# OpenSprinkler_v142.net
KiCad netlist of a schematic drawn in EAGLE
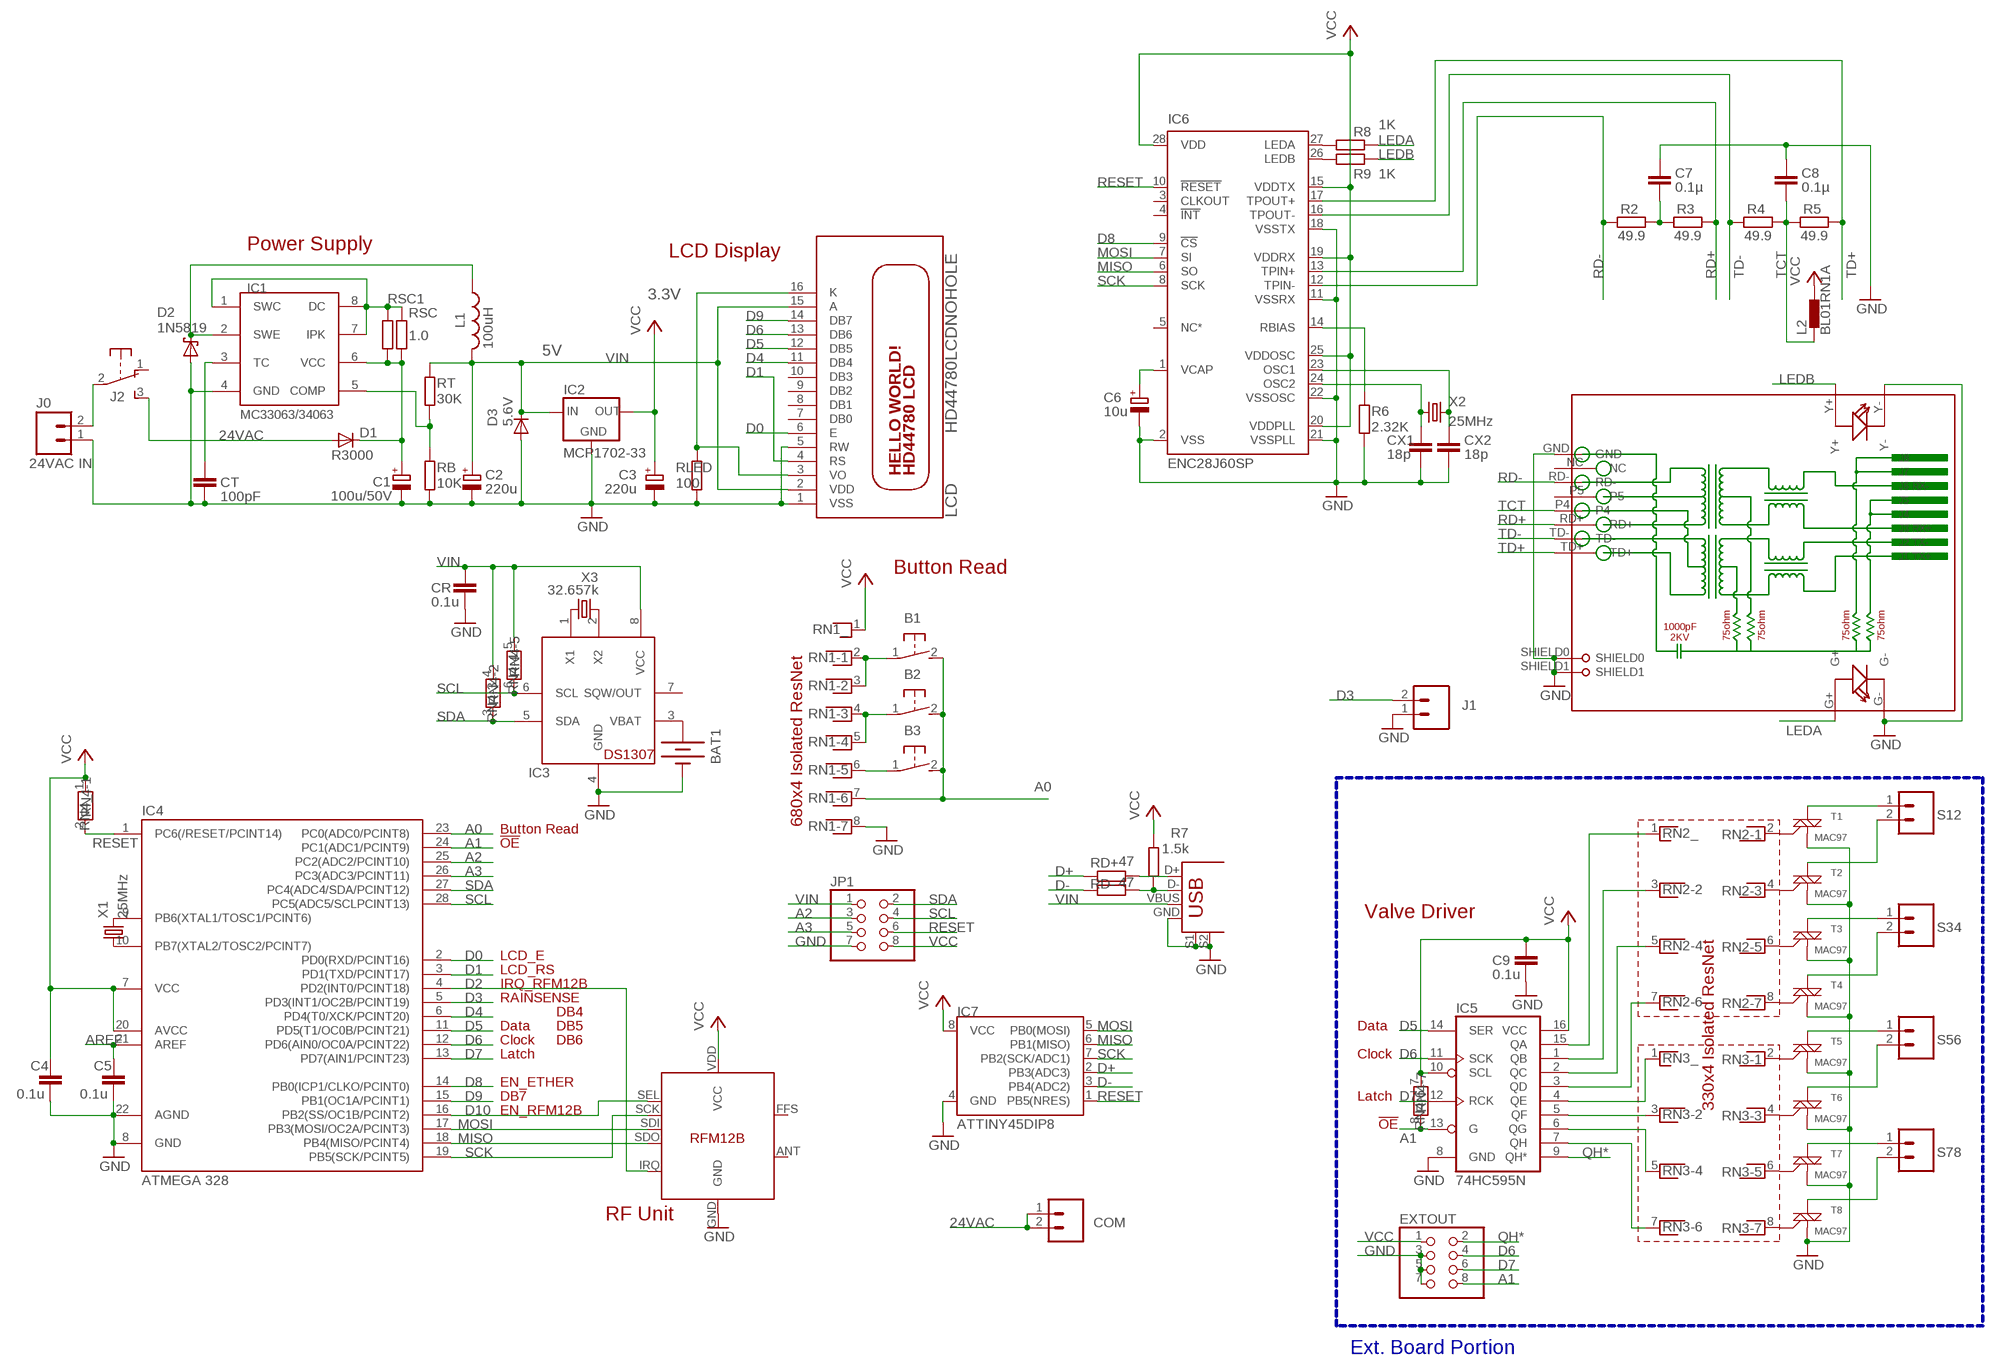
[diagram p0: schematic, sheet 1]

(export (version "E")
  (design (tool "Eeschema 10.0.6"))
  (components
    (comp (ref "B1")
      (value "31-XX")
      (footprint "eagle-import:B3F-31XX")
      (libsource (lib "eagle-import") (part "31-XX"))
    )
    (comp (ref "B2")
      (value "31-XX")
      (footprint "eagle-import:B3F-31XX")
      (libsource (lib "eagle-import") (part "31-XX"))
    )
    (comp (ref "B3")
      (value "31-XX")
      (footprint "eagle-import:B3F-31XX")
      (libsource (lib "eagle-import") (part "31-XX"))
    )
    (comp (ref "BAT1")
      (value "BATTERY12PTH")
      (footprint "eagle-import:BATTCON_12MM_PTH")
      (libsource (lib "eagle-import") (part "BATTERY12PTH"))
    )
    (comp (ref "C1")
      (value "100u/50V")
      (footprint "eagle-import:E3,5-8")
      (libsource (lib "eagle-import") (part "CPOL-EUE3.5-8"))
    )
    (comp (ref "C2")
      (value "220u")
      (footprint "eagle-import:E2-5")
      (libsource (lib "eagle-import") (part "CPOL-EUE2-5"))
    )
    (comp (ref "C3")
      (value "220u")
      (footprint "eagle-import:E2-5")
      (libsource (lib "eagle-import") (part "CPOL-EUE2-5"))
    )
    (comp (ref "C4")
      (value "0.1u")
      (footprint "eagle-import:C025-024X044")
      (libsource (lib "eagle-import") (part "C-EU025-024X044"))
    )
    (comp (ref "C5")
      (value "0.1u")
      (footprint "eagle-import:C025-024X044")
      (libsource (lib "eagle-import") (part "C-EU025-024X044"))
    )
    (comp (ref "C6")
      (value "10u")
      (footprint "eagle-import:E1,8-4")
      (libsource (lib "eagle-import") (part "CPOL-EUE1.8-4"))
    )
    (comp (ref "C7")
      (value "0.1µ")
      (footprint "eagle-import:C025-024X044")
      (libsource (lib "eagle-import") (part "resistor_C-EU025-024X044"))
    )
    (comp (ref "C8")
      (value "0.1µ")
      (footprint "eagle-import:C025-024X044")
      (libsource (lib "eagle-import") (part "resistor_C-EU025-024X044"))
    )
    (comp (ref "C9")
      (value "0.1u")
      (footprint "eagle-import:C025-024X044")
      (libsource (lib "eagle-import") (part "C-EU025-024X044"))
    )
    (comp (ref "COM")
      (value "M025MM")
      (footprint "eagle-import:SCREWTERMINAL-5MM-2")
      (libsource (lib "eagle-import") (part "M025MM"))
    )
    (comp (ref "CR")
      (value "0.1u")
      (footprint "eagle-import:C025-024X044")
      (libsource (lib "eagle-import") (part "C-EU025-024X044"))
    )
    (comp (ref "CT")
      (value "100pF")
      (footprint "eagle-import:C025-024X044")
      (libsource (lib "eagle-import") (part "C-EU025-024X044"))
    )
    (comp (ref "CX1")
      (value "18p")
      (footprint "eagle-import:C025-024X044")
      (libsource (lib "eagle-import") (part "resistor_C-EU025-024X044"))
    )
    (comp (ref "CX2")
      (value "18p")
      (footprint "eagle-import:C025-024X044")
      (libsource (lib "eagle-import") (part "resistor_C-EU025-024X044"))
    )
    (comp (ref "D1")
      (value "R3000")
      (footprint "eagle-import:DO41-7.6")
      (libsource (lib "eagle-import") (part "DIODE-DO41-7.6"))
    )
    (comp (ref "D2")
      (value "1N5819")
      (footprint "eagle-import:DO41-7.6")
      (libsource (lib "eagle-import") (part "1N5817-B"))
    )
    (comp (ref "D3")
      (value "5.6V")
      (footprint "eagle-import:DO35-7")
      (libsource (lib "eagle-import") (part "1N4148DO35-7"))
    )
    (comp (ref "EXTOUT")
      (value "PINHD-2X4")
      (footprint "eagle-import:2X04")
      (libsource (lib "eagle-import") (part "PINHD-2X4"))
    )
    (comp (ref "IC1")
      (value "MC33063/MC34063P")
      (footprint "eagle-import:DIL08")
      (libsource (lib "eagle-import") (part "MC33063/MC34063P"))
    )
    (comp (ref "IC2")
      (value "MCP1702-33")
      (footprint "eagle-import:TO92-INLINE")
      (libsource (lib "eagle-import") (part "MCP1700INLINE"))
    )
    (comp (ref "IC3")
      (value "DS1307")
      (footprint "eagle-import:DIL08")
      (libsource (lib "eagle-import") (part "DS1307"))
    )
    (comp (ref "IC4")
      (value "ATMEGA 328")
      (footprint "eagle-import:DIL28-3")
      (libsource (lib "eagle-import") (part "ATMEGA48/88/168-PU"))
    )
    (comp (ref "IC5")
      (value "74HC595N")
      (footprint "eagle-import:DIL16")
      (libsource (lib "eagle-import") (part "74595NLS"))
    )
    (comp (ref "IC6")
      (value "ENC28J60SP")
      (footprint "eagle-import:DIL28-3")
      (fields (field (name "MF") "MICROCHIP") (field (name "MPN") "ENC28J60/SP"))
      (libsource (lib "eagle-import") (part "ENC28J60SP"))
    )
    (comp (ref "IC7")
      (value "ATTINY45DIP8")
      (footprint "eagle-import:DIP08")
      (libsource (lib "eagle-import") (part "ATTINY45DIP8"))
    )
    (comp (ref "IC8")
      (value "RFM12B")
      (footprint "eagle-import:RFM12B")
      (libsource (lib "eagle-import") (part "RFM12B"))
    )
    (comp (ref "J0")
      (value "24VAC IN")
      (footprint "eagle-import:SCREWTERMINAL-5MM-2")
      (libsource (lib "eagle-import") (part "M025MM"))
    )
    (comp (ref "J1")
      (value "M025MM")
      (footprint "eagle-import:SCREWTERMINAL-5MM-2")
      (libsource (lib "eagle-import") (part "M025MM"))
    )
    (comp (ref "J2")
      (value "EG1206")
      (footprint "eagle-import:EG1206")
      (libsource (lib "eagle-import") (part "EG1206"))
    )
    (comp (ref "JP1")
      (value "PINHD-2X4")
      (footprint "eagle-import:2X04")
      (libsource (lib "eagle-import") (part "PINHD-2X4"))
    )
    (comp (ref "L1")
      (value "100uH")
      (footprint "eagle-import:6000-XXXX-RC")
      (libsource (lib "eagle-import") (part "L-US6000-XXX-RC"))
    )
    (comp (ref "L2")
      (value "BL01RN1A")
      (footprint "eagle-import:BL01RN1A")
      (libsource (lib "eagle-import") (part "BL01RN1A"))
    )
    (comp (ref "LCD")
      (value "HD44780LCDNOHOLE")
      (footprint "eagle-import:LCD1602A")
      (libsource (lib "eagle-import") (part "HD44780LCDNOHOLE"))
    )
    (comp (ref "R2")
      (value "49.9")
      (footprint "eagle-import:0204_7")
      (libsource (lib "eagle-import") (part "R-EU_0204/7"))
    )
    (comp (ref "R3")
      (value "49.9")
      (footprint "eagle-import:0204_7")
      (libsource (lib "eagle-import") (part "R-EU_0204/7"))
    )
    (comp (ref "R4")
      (value "49.9")
      (footprint "eagle-import:0204_7")
      (libsource (lib "eagle-import") (part "R-EU_0204/7"))
    )
    (comp (ref "R5")
      (value "49.9")
      (footprint "eagle-import:0204_7")
      (libsource (lib "eagle-import") (part "R-EU_0204/7"))
    )
    (comp (ref "R6")
      (value "2.32K")
      (footprint "eagle-import:0204_7")
      (libsource (lib "eagle-import") (part "R-EU_0204/7"))
    )
    (comp (ref "R7")
      (value "1.5k")
      (footprint "eagle-import:0204_7")
      (libsource (lib "eagle-import") (part "R-EU_0204/7"))
    )
    (comp (ref "R8")
      (value "1K")
      (footprint "eagle-import:0204_7")
      (libsource (lib "eagle-import") (part "R-EU_0204/7"))
    )
    (comp (ref "R9")
      (value "1K")
      (footprint "eagle-import:0204_7")
      (libsource (lib "eagle-import") (part "R-EU_0204/7"))
    )
    (comp (ref "RB")
      (value "10K")
      (footprint "eagle-import:0204_7")
      (libsource (lib "eagle-import") (part "R-EU_0204/7"))
    )
    (comp (ref "RD+")
      (value "47")
      (footprint "eagle-import:0204_7")
      (libsource (lib "eagle-import") (part "R-EU_0204/7"))
    )
    (comp (ref "RD-")
      (value "47")
      (footprint "eagle-import:0204_7")
      (libsource (lib "eagle-import") (part "R-EU_0204/7"))
    )
    (comp (ref "RJ1")
      (value "HR911105A")
      (footprint "eagle-import:HR911105A")
      (libsource (lib "eagle-import") (part "HR911105A"))
    )
    (comp (ref "RLED")
      (value "100")
      (footprint "eagle-import:0204_7")
      (libsource (lib "eagle-import") (part "R-EU_0204/7"))
    )
    (comp (ref "RN1")
      (value "RNX7")
      (footprint "eagle-import:RN-8")
      (libsource (lib "eagle-import") (part "RNX7"))
    )
    (comp (ref "RN2")
      (value "RNX7")
      (footprint "eagle-import:RN-8")
      (libsource (lib "eagle-import") (part "RNX7"))
    )
    (comp (ref "RN3")
      (value "RNX7")
      (footprint "eagle-import:RN-8")
      (libsource (lib "eagle-import") (part "RNX7"))
    )
    (comp (ref "RN4")
      (value "RNX7")
      (footprint "eagle-import:RN-8")
      (libsource (lib "eagle-import") (part "RNX7"))
    )
    (comp (ref "RSC")
      (value "1.0")
      (footprint "eagle-import:0204_7")
      (libsource (lib "eagle-import") (part "R-EU_0204/7"))
    )
    (comp (ref "RSC1")
      (value "1.0")
      (footprint "eagle-import:0204_7")
      (libsource (lib "eagle-import") (part "R-EU_0204/7"))
    )
    (comp (ref "RT")
      (value "30K")
      (footprint "eagle-import:0204_7")
      (libsource (lib "eagle-import") (part "R-EU_0204/7"))
    )
    (comp (ref "S12")
      (value "M025MM")
      (footprint "eagle-import:SCREWTERMINAL-5MM-2")
      (libsource (lib "eagle-import") (part "M025MM"))
    )
    (comp (ref "S34")
      (value "M025MM")
      (footprint "eagle-import:SCREWTERMINAL-5MM-2")
      (libsource (lib "eagle-import") (part "M025MM"))
    )
    (comp (ref "S56")
      (value "M025MM")
      (footprint "eagle-import:SCREWTERMINAL-5MM-2")
      (libsource (lib "eagle-import") (part "M025MM"))
    )
    (comp (ref "S78")
      (value "M025MM")
      (footprint "eagle-import:SCREWTERMINAL-5MM-2")
      (libsource (lib "eagle-import") (part "M025MM"))
    )
    (comp (ref "T1")
      (value "MAC97")
      (footprint "eagle-import:TO-92")
      (libsource (lib "eagle-import") (part "LX807DE"))
    )
    (comp (ref "T2")
      (value "MAC97")
      (footprint "eagle-import:TO-92")
      (libsource (lib "eagle-import") (part "LX807DE"))
    )
    (comp (ref "T3")
      (value "MAC97")
      (footprint "eagle-import:TO-92")
      (libsource (lib "eagle-import") (part "LX807DE"))
    )
    (comp (ref "T4")
      (value "MAC97")
      (footprint "eagle-import:TO-92")
      (libsource (lib "eagle-import") (part "LX807DE"))
    )
    (comp (ref "T5")
      (value "MAC97")
      (footprint "eagle-import:TO-92")
      (libsource (lib "eagle-import") (part "LX807DE"))
    )
    (comp (ref "T6")
      (value "MAC97")
      (footprint "eagle-import:TO-92")
      (libsource (lib "eagle-import") (part "LX807DE"))
    )
    (comp (ref "T7")
      (value "MAC97")
      (footprint "eagle-import:TO-92")
      (libsource (lib "eagle-import") (part "LX807DE"))
    )
    (comp (ref "T8")
      (value "MAC97")
      (footprint "eagle-import:TO-92")
      (libsource (lib "eagle-import") (part "LX807DE"))
    )
    (comp (ref "USB")
      (value "USB+SHIELD")
      (footprint "eagle-import:USB-B-PTH")
      (libsource (lib "eagle-import") (part "USB+SHIELD"))
    )
    (comp (ref "X1")
      (value "25MHz")
      (footprint "eagle-import:HC49US")
      (libsource (lib "eagle-import") (part "CRYSTALHC49US"))
    )
    (comp (ref "X2")
      (value "25MHz")
      (footprint "eagle-import:HC49US")
      (libsource (lib "eagle-import") (part "CRYSTALHC49US"))
    )
    (comp (ref "X3")
      (value "32.657k")
      (footprint "eagle-import:TC26H")
      (libsource (lib "eagle-import") (part "crystal_CRYSTALTC26H"))
    )
  )
  (nets
    (net (code "1") (name "/24VAC") (class "Default")
      (node (ref "COM") (pin "1") (pinfunction "1_1") (pintype "passive"))
      (node (ref "COM") (pin "2") (pinfunction "2_2") (pintype "passive"))
      (node (ref "D1") (pin "A") (pinfunction "A_A") (pintype "passive"))
      (node (ref "J2") (pin "3") (pinfunction "S_3") (pintype "passive"))
    )
    (net (code "2") (name "/A0") (class "Default")
      (node (ref "B1") (pin "2") (pinfunction "S_2") (pintype "passive"))
      (node (ref "B2") (pin "2") (pinfunction "S_2") (pintype "passive"))
      (node (ref "B3") (pin "2") (pinfunction "S_2") (pintype "passive"))
      (node (ref "IC4") (pin "23") (pinfunction "PC0(ADC0/PCINT8)_23") (pintype "bidirectional"))
      (node (ref "RN1") (pin "7") (pinfunction "1_7") (pintype "passive"))
    )
    (net (code "3") (name "/A1") (class "Default")
      (node (ref "EXTOUT") (pin "8") (pinfunction "8_8") (pintype "passive"))
      (node (ref "IC4") (pin "24") (pinfunction "PC1(ADC1/PCINT9)_24") (pintype "bidirectional"))
      (node (ref "IC5") (pin "13") (pinfunction "G_13") (pintype "input"))
      (node (ref "RN4") (pin "8") (pinfunction "1_8") (pintype "passive"))
    )
    (net (code "4") (name "/A2") (class "Default")
      (node (ref "IC4") (pin "25") (pinfunction "PC2(ADC2/PCINT10)_25") (pintype "bidirectional"))
      (node (ref "JP1") (pin "3") (pinfunction "3_3") (pintype "passive"))
    )
    (net (code "5") (name "/A3") (class "Default")
      (node (ref "IC4") (pin "26") (pinfunction "PC3(ADC3/PCINT11)_26") (pintype "bidirectional"))
      (node (ref "JP1") (pin "5") (pinfunction "5_5") (pintype "passive"))
    )
    (net (code "6") (name "/AREF") (class "Default")
      (node (ref "C5") (pin "1") (pinfunction "1_1") (pintype "passive"))
      (node (ref "IC4") (pin "21") (pinfunction "AREF_21") (pintype "passive"))
    )
    (net (code "7") (name "/D+") (class "Default")
      (node (ref "IC7") (pin "2") (pinfunction "PB3(ADC3)_2") (pintype "bidirectional"))
      (node (ref "RD+") (pin "1") (pinfunction "1_1") (pintype "passive"))
    )
    (net (code "8") (name "/D-") (class "Default")
      (node (ref "IC7") (pin "3") (pinfunction "PB4(ADC2)_3") (pintype "bidirectional"))
      (node (ref "RD-") (pin "1") (pinfunction "1_1") (pintype "passive"))
    )
    (net (code "9") (name "/D0") (class "Default")
      (node (ref "IC4") (pin "2") (pinfunction "PD0(RXD/PCINT16)_2") (pintype "bidirectional"))
      (node (ref "LCD") (pin "6") (pinfunction "E_6") (pintype "input"))
    )
    (net (code "10") (name "/D1") (class "Default")
      (node (ref "IC4") (pin "3") (pinfunction "PD1(TXD/PCINT17)_3") (pintype "bidirectional"))
      (node (ref "LCD") (pin "4") (pinfunction "RS_4") (pintype "input"))
    )
    (net (code "11") (name "/D2") (class "Default")
      (node (ref "IC4") (pin "4") (pinfunction "PD2(INT0/PCINT18)_4") (pintype "bidirectional"))
      (node (ref "IC8") (pin "IRQ") (pinfunction "IRQ_IRQ") (pintype "open_collector"))
    )
    (net (code "12") (name "/D3") (class "Default")
      (node (ref "IC4") (pin "5") (pinfunction "PD3(INT1/OC2B/PCINT19)_5") (pintype "bidirectional"))
      (node (ref "J1") (pin "2") (pinfunction "2_2") (pintype "passive"))
    )
    (net (code "13") (name "/D4") (class "Default")
      (node (ref "IC4") (pin "6") (pinfunction "PD4(T0/XCK/PCINT20)_6") (pintype "bidirectional"))
      (node (ref "LCD") (pin "11") (pinfunction "DB4_11") (pintype "bidirectional"))
    )
    (net (code "14") (name "/D5") (class "Default")
      (node (ref "IC4") (pin "11") (pinfunction "PD5(T1/OC0B/PCINT21)_11") (pintype "bidirectional"))
      (node (ref "IC5") (pin "14") (pinfunction "SER_14") (pintype "input"))
      (node (ref "LCD") (pin "12") (pinfunction "DB5_12") (pintype "bidirectional"))
    )
    (net (code "15") (name "/D6") (class "Default")
      (node (ref "EXTOUT") (pin "4") (pinfunction "4_4") (pintype "passive"))
      (node (ref "IC4") (pin "12") (pinfunction "PD6(AIN0/OC0A/PCINT22)_12") (pintype "bidirectional"))
      (node (ref "IC5") (pin "11") (pinfunction "SCK_11") (pintype "input"))
      (node (ref "LCD") (pin "13") (pinfunction "DB6_13") (pintype "bidirectional"))
    )
    (net (code "16") (name "/D7") (class "Default")
      (node (ref "EXTOUT") (pin "6") (pinfunction "6_6") (pintype "passive"))
      (node (ref "IC4") (pin "13") (pinfunction "PD7(AIN1/PCINT23)_13") (pintype "bidirectional"))
      (node (ref "IC5") (pin "12") (pinfunction "RCK_12") (pintype "input"))
    )
    (net (code "17") (name "/D8") (class "Default")
      (node (ref "IC4") (pin "14") (pinfunction "PB0(ICP1/CLKO/PCINT0)_14") (pintype "bidirectional"))
      (node (ref "IC6") (pin "9") (pinfunction "~{CS}_9") (pintype "input"))
    )
    (net (code "18") (name "/D9") (class "Default")
      (node (ref "IC4") (pin "15") (pinfunction "PB1(OC1A/PCINT1)_15") (pintype "bidirectional"))
      (node (ref "LCD") (pin "14") (pinfunction "DB7_14") (pintype "bidirectional"))
    )
    (net (code "19") (name "/D10") (class "Default")
      (node (ref "IC4") (pin "16") (pinfunction "PB2(SS/OC1B/PCINT2)_16") (pintype "bidirectional"))
      (node (ref "IC8") (pin "SEL") (pinfunction "SEL_SEL") (pintype "input"))
    )
    (net (code "20") (name "/LEDA") (class "Default")
      (node (ref "R8") (pin "2") (pinfunction "2_2") (pintype "passive"))
      (node (ref "RJ1") (pin "G+") (pinfunction "G+_G+") (pintype "bidirectional"))
    )
    (net (code "21") (name "/LEDB") (class "Default")
      (node (ref "R9") (pin "2") (pinfunction "2_2") (pintype "passive"))
      (node (ref "RJ1") (pin "Y+") (pinfunction "Y+_Y+") (pintype "bidirectional"))
    )
    (net (code "22") (name "/MISO") (class "Default")
      (node (ref "IC4") (pin "18") (pinfunction "PB4(MISO/PCINT4)_18") (pintype "bidirectional"))
      (node (ref "IC6") (pin "6") (pinfunction "SO_6") (pintype "output"))
      (node (ref "IC7") (pin "6") (pinfunction "PB1(MISO)_6") (pintype "bidirectional"))
      (node (ref "IC8") (pin "SDO") (pinfunction "SDO_SDO") (pintype "output"))
    )
    (net (code "23") (name "/MOSI") (class "Default")
      (node (ref "IC4") (pin "17") (pinfunction "PB3(MOSI/OC2A/PCINT3)_17") (pintype "bidirectional"))
      (node (ref "IC6") (pin "7") (pinfunction "SI_7") (pintype "input"))
      (node (ref "IC7") (pin "5") (pinfunction "PB0(MOSI)_5") (pintype "bidirectional"))
      (node (ref "IC8") (pin "SDI") (pinfunction "SDI_SDI") (pintype "input"))
    )
    (net (code "24") (name "/QH*") (class "Default")
      (node (ref "EXTOUT") (pin "2") (pinfunction "2_2") (pintype "passive"))
      (node (ref "IC5") (pin "9") (pinfunction "QH*_9") (pintype "tri_state"))
    )
    (net (code "25") (name "/RD+") (class "Default")
      (node (ref "IC6") (pin "13") (pinfunction "TPIN+_13") (pintype "input"))
      (node (ref "R3") (pin "2") (pinfunction "2_2") (pintype "passive"))
      (node (ref "RJ1") (pin "RD+") (pinfunction "RD+_RD+") (pintype "bidirectional"))
    )
    (net (code "26") (name "/RD-") (class "Default")
      (node (ref "IC6") (pin "12") (pinfunction "TPIN-_12") (pintype "input"))
      (node (ref "R2") (pin "1") (pinfunction "1_1") (pintype "passive"))
      (node (ref "RJ1") (pin "RD-") (pinfunction "RD-_RD-") (pintype "bidirectional"))
    )
    (net (code "27") (name "/RESET") (class "Default")
      (node (ref "IC4") (pin "1") (pinfunction "PC6(/RESET/PCINT14)_1") (pintype "bidirectional"))
      (node (ref "IC6") (pin "10") (pinfunction "~{RESET}_10") (pintype "input"))
      (node (ref "IC7") (pin "1") (pinfunction "PB5(NRES)_1") (pintype "bidirectional"))
      (node (ref "JP1") (pin "6") (pinfunction "6_6") (pintype "passive"))
      (node (ref "RN4") (pin "2") (pinfunction "1_2") (pintype "passive"))
    )
    (net (code "28") (name "/SCK") (class "Default")
      (node (ref "IC4") (pin "19") (pinfunction "PB5(SCK/PCINT5)_19") (pintype "bidirectional"))
      (node (ref "IC6") (pin "8") (pinfunction "SCK_8") (pintype "input"))
      (node (ref "IC7") (pin "7") (pinfunction "PB2(SCK/ADC1)_7") (pintype "bidirectional"))
      (node (ref "IC8") (pin "SCK") (pinfunction "SCK_SCK") (pintype "input"))
    )
    (net (code "29") (name "/SCL") (class "Default")
      (node (ref "IC3") (pin "6") (pinfunction "SCL_6") (pintype "bidirectional"))
      (node (ref "IC4") (pin "28") (pinfunction "PC5(ADC5/SCLPCINT13)_28") (pintype "bidirectional"))
      (node (ref "JP1") (pin "4") (pinfunction "4_4") (pintype "passive"))
      (node (ref "RN4") (pin "6") (pinfunction "1_6") (pintype "passive"))
    )
    (net (code "30") (name "/SDA") (class "Default")
      (node (ref "IC3") (pin "5") (pinfunction "SDA_5") (pintype "bidirectional"))
      (node (ref "IC4") (pin "27") (pinfunction "PC4(ADC4/SDA/PCINT12)_27") (pintype "bidirectional"))
      (node (ref "JP1") (pin "2") (pinfunction "2_2") (pintype "passive"))
      (node (ref "RN4") (pin "3") (pinfunction "1_3") (pintype "passive"))
    )
    (net (code "31") (name "/TCT") (class "Default")
      (node (ref "C8") (pin "2") (pinfunction "2_2") (pintype "passive"))
      (node (ref "L2") (pin "1") (pinfunction "1_1") (pintype "passive"))
      (node (ref "R4") (pin "2") (pinfunction "2_2") (pintype "passive"))
      (node (ref "R5") (pin "1") (pinfunction "1_1") (pintype "passive"))
      (node (ref "RJ1") (pin "P4") (pinfunction "P4_P4") (pintype "bidirectional"))
    )
    (net (code "32") (name "/TD+") (class "Default")
      (node (ref "IC6") (pin "17") (pinfunction "TPOUT+_17") (pintype "output"))
      (node (ref "R5") (pin "2") (pinfunction "2_2") (pintype "passive"))
      (node (ref "RJ1") (pin "TD+") (pinfunction "TD+_TD+") (pintype "bidirectional"))
    )
    (net (code "33") (name "/TD-") (class "Default")
      (node (ref "IC6") (pin "16") (pinfunction "TPOUT-_16") (pintype "output"))
      (node (ref "R4") (pin "1") (pinfunction "1_1") (pintype "passive"))
      (node (ref "RJ1") (pin "TD-") (pinfunction "TD-_TD-") (pintype "bidirectional"))
    )
    (net (code "34") (name "/VIN") (class "Default")
      (node (ref "C2") (pin "+") (pinfunction "+_+") (pintype "passive"))
      (node (ref "CR") (pin "1") (pinfunction "1_1") (pintype "passive"))
      (node (ref "D3") (pin "C") (pinfunction "C_C") (pintype "passive"))
      (node (ref "IC2") (pin "2") (pinfunction "IN_2") (pintype "input"))
      (node (ref "IC3") (pin "8") (pinfunction "VCC_8") (pintype "power_in"))
      (node (ref "JP1") (pin "1") (pinfunction "1_1") (pintype "passive"))
      (node (ref "L1") (pin "2") (pinfunction "2_2") (pintype "passive"))
      (node (ref "LCD") (pin "15") (pinfunction "A_15") (pintype "input"))
      (node (ref "LCD") (pin "2") (pinfunction "VDD_2") (pintype "power_in"))
      (node (ref "RN4") (pin "4") (pinfunction "1_4") (pintype "passive"))
      (node (ref "RN4") (pin "5") (pinfunction "1_5") (pintype "passive"))
      (node (ref "RT") (pin "1") (pinfunction "1_1") (pintype "passive"))
      (node (ref "USB") (pin "VBUS") (pinfunction "VBUS_VBUS") (pintype "bidirectional"))
    )
    (net (code "35") (name "GND") (class "Default")
      (node (ref "BAT1") (pin "GND") (pinfunction "-_GND") (pintype "power_in"))
      (node (ref "C1") (pin "-") (pinfunction "-_-") (pintype "passive"))
      (node (ref "C2") (pin "-") (pinfunction "-_-") (pintype "passive"))
      (node (ref "C3") (pin "-") (pinfunction "-_-") (pintype "passive"))
      (node (ref "C4") (pin "2") (pinfunction "2_2") (pintype "passive"))
      (node (ref "C5") (pin "2") (pinfunction "2_2") (pintype "passive"))
      (node (ref "C6") (pin "-") (pinfunction "-_-") (pintype "passive"))
      (node (ref "C7") (pin "1") (pinfunction "1_1") (pintype "passive"))
      (node (ref "C8") (pin "1") (pinfunction "1_1") (pintype "passive"))
      (node (ref "C9") (pin "2") (pinfunction "2_2") (pintype "passive"))
      (node (ref "CR") (pin "2") (pinfunction "2_2") (pintype "passive"))
      (node (ref "CT") (pin "2") (pinfunction "2_2") (pintype "passive"))
      (node (ref "CX1") (pin "2") (pinfunction "2_2") (pintype "passive"))
      (node (ref "CX2") (pin "2") (pinfunction "2_2") (pintype "passive"))
      (node (ref "D2") (pin "A") (pinfunction "A_A") (pintype "passive"))
      (node (ref "D3") (pin "A") (pinfunction "A_A") (pintype "passive"))
      (node (ref "EXTOUT") (pin "3") (pinfunction "3_3") (pintype "passive"))
      (node (ref "EXTOUT") (pin "5") (pinfunction "5_5") (pintype "passive"))
      (node (ref "EXTOUT") (pin "7") (pinfunction "7_7") (pintype "passive"))
      (node (ref "IC1") (pin "4") (pinfunction "GND_4") (pintype "power_in"))
      (node (ref "IC2") (pin "1") (pinfunction "GND_1") (pintype "input"))
      (node (ref "IC3") (pin "4") (pinfunction "GND_4") (pintype "power_in"))
      (node (ref "IC4") (pin "22") (pinfunction "AGND_22") (pintype "power_in"))
      (node (ref "IC4") (pin "8") (pinfunction "GND_8") (pintype "power_in"))
      (node (ref "IC5") (pin "8") (pinfunction "GND_8") (pintype "power_in"))
      (node (ref "IC6") (pin "11") (pinfunction "VSSRX_11") (pintype "input"))
      (node (ref "IC6") (pin "18") (pinfunction "VSSTX_18") (pintype "input"))
      (node (ref "IC6") (pin "2") (pinfunction "VSS_2") (pintype "input"))
      (node (ref "IC6") (pin "21") (pinfunction "VSSPLL_21") (pintype "input"))
      (node (ref "IC6") (pin "22") (pinfunction "VSSOSC_22") (pintype "input"))
      (node (ref "IC7") (pin "4") (pinfunction "GND_4") (pintype "bidirectional"))
      (node (ref "IC8") (pin "GND") (pinfunction "GND_GND") (pintype "power_in"))
      (node (ref "J0") (pin "1") (pinfunction "1_1") (pintype "passive"))
      (node (ref "J1") (pin "1") (pinfunction "1_1") (pintype "passive"))
      (node (ref "JP1") (pin "7") (pinfunction "7_7") (pintype "passive"))
      (node (ref "LCD") (pin "1") (pinfunction "VSS_1") (pintype "power_in"))
      (node (ref "LCD") (pin "5") (pinfunction "RW_5") (pintype "input"))
      (node (ref "R6") (pin "2") (pinfunction "2_2") (pintype "passive"))
      (node (ref "RB") (pin "2") (pinfunction "2_2") (pintype "passive"))
      (node (ref "RJ1") (pin "G-") (pinfunction "G-_G-") (pintype "bidirectional"))
      (node (ref "RJ1") (pin "GND") (pinfunction "GND_GND") (pintype "bidirectional"))
      (node (ref "RJ1") (pin "SHIELD0") (pinfunction "SHIELD0_SHIELD0") (pintype "bidirectional"))
      (node (ref "RJ1") (pin "SHIELD1") (pinfunction "SHIELD1_SHIELD1") (pintype "bidirectional"))
      (node (ref "RJ1") (pin "Y-") (pinfunction "Y-_Y-") (pintype "bidirectional"))
      (node (ref "RLED") (pin "2") (pinfunction "2_2") (pintype "passive"))
      (node (ref "RN1") (pin "8") (pinfunction "1_8") (pintype "passive"))
      (node (ref "T1") (pin "1") (pinfunction "M1_1") (pintype "bidirectional"))
      (node (ref "T2") (pin "1") (pinfunction "M1_1") (pintype "bidirectional"))
      (node (ref "T3") (pin "1") (pinfunction "M1_1") (pintype "bidirectional"))
      (node (ref "T4") (pin "1") (pinfunction "M1_1") (pintype "bidirectional"))
      (node (ref "T5") (pin "1") (pinfunction "M1_1") (pintype "bidirectional"))
      (node (ref "T6") (pin "1") (pinfunction "M1_1") (pintype "bidirectional"))
      (node (ref "T7") (pin "1") (pinfunction "M1_1") (pintype "bidirectional"))
      (node (ref "T8") (pin "1") (pinfunction "M1_1") (pintype "bidirectional"))
      (node (ref "USB") (pin "GND") (pinfunction "GND_GND") (pintype "bidirectional"))
      (node (ref "USB") (pin "S1") (pinfunction "P$1_S1") (pintype "bidirectional"))
      (node (ref "USB") (pin "S2") (pinfunction "P$2_S2") (pintype "bidirectional"))
    )
    (net (code "36") (name "Net-(B1-P)") (class "Default")
      (node (ref "B1") (pin "1") (pinfunction "P_1") (pintype "passive"))
      (node (ref "RN1") (pin "2") (pinfunction "1_2") (pintype "passive"))
      (node (ref "RN1") (pin "3") (pinfunction "1_3") (pintype "passive"))
    )
    (net (code "37") (name "Net-(B2-P)") (class "Default")
      (node (ref "B2") (pin "1") (pinfunction "P_1") (pintype "passive"))
      (node (ref "RN1") (pin "4") (pinfunction "1_4") (pintype "passive"))
      (node (ref "RN1") (pin "5") (pinfunction "1_5") (pintype "passive"))
    )
    (net (code "38") (name "Net-(B3-P)") (class "Default")
      (node (ref "B3") (pin "1") (pinfunction "P_1") (pintype "passive"))
      (node (ref "RN1") (pin "6") (pinfunction "1_6") (pintype "passive"))
    )
    (net (code "39") (name "Net-(BAT1-+)") (class "Default")
      (node (ref "BAT1") (pin "VCC@1") (pinfunction "+_VCC@1") (pintype "power_in"))
      (node (ref "IC3") (pin "3") (pinfunction "VBAT_3") (pintype "power_in"))
    )
    (net (code "40") (name "Net-(C7-Pad2)") (class "Default")
      (node (ref "C7") (pin "2") (pinfunction "2_2") (pintype "passive"))
      (node (ref "R2") (pin "2") (pinfunction "2_2") (pintype "passive"))
      (node (ref "R3") (pin "1") (pinfunction "1_1") (pintype "passive"))
    )
    (net (code "41") (name "Net-(IC1-COMP)") (class "Default")
      (node (ref "IC1") (pin "5") (pinfunction "COMP_5") (pintype "input"))
      (node (ref "RB") (pin "1") (pinfunction "1_1") (pintype "passive"))
      (node (ref "RT") (pin "2") (pinfunction "2_2") (pintype "passive"))
    )
    (net (code "42") (name "Net-(IC1-DC)") (class "Default")
      (node (ref "IC1") (pin "1") (pinfunction "SWC_1") (pintype "input"))
      (node (ref "IC1") (pin "7") (pinfunction "IPK_7") (pintype "bidirectional"))
      (node (ref "IC1") (pin "8") (pinfunction "DC_8") (pintype "input"))
      (node (ref "RSC") (pin "1") (pinfunction "1_1") (pintype "passive"))
      (node (ref "RSC1") (pin "1") (pinfunction "1_1") (pintype "passive"))
    )
    (net (code "43") (name "Net-(IC1-SWE)") (class "Default")
      (node (ref "D2") (pin "C") (pinfunction "C_C") (pintype "passive"))
      (node (ref "IC1") (pin "2") (pinfunction "SWE_2") (pintype "input"))
      (node (ref "L1") (pin "1") (pinfunction "1_1") (pintype "passive"))
    )
    (net (code "44") (name "Net-(IC1-TC)") (class "Default")
      (node (ref "CT") (pin "1") (pinfunction "1_1") (pintype "passive"))
      (node (ref "IC1") (pin "3") (pinfunction "TC_3") (pintype "input"))
    )
    (net (code "45") (name "Net-(IC1-VCC)") (class "Default")
      (node (ref "C1") (pin "+") (pinfunction "+_+") (pintype "passive"))
      (node (ref "D1") (pin "C") (pinfunction "C_C") (pintype "passive"))
      (node (ref "IC1") (pin "6") (pinfunction "VCC_6") (pintype "power_in"))
      (node (ref "RSC") (pin "2") (pinfunction "2_2") (pintype "passive"))
      (node (ref "RSC1") (pin "2") (pinfunction "2_2") (pintype "passive"))
    )
    (net (code "46") (name "Net-(IC3-X1)") (class "Default")
      (node (ref "IC3") (pin "1") (pinfunction "X1_1") (pintype "passive"))
      (node (ref "X3") (pin "1") (pinfunction "1_1") (pintype "passive"))
    )
    (net (code "47") (name "Net-(IC3-X2)") (class "Default")
      (node (ref "IC3") (pin "2") (pinfunction "X2_2") (pintype "passive"))
      (node (ref "X3") (pin "2") (pinfunction "2_2") (pintype "passive"))
    )
    (net (code "48") (name "Net-(IC4-PB6(XTAL1{slash}TOSC1{slash}PCINT6))") (class "Default")
      (node (ref "IC4") (pin "9") (pinfunction "PB6(XTAL1/TOSC1/PCINT6)_9") (pintype "bidirectional"))
      (node (ref "X1") (pin "2") (pinfunction "2_2") (pintype "passive"))
    )
    (net (code "49") (name "Net-(IC4-PB7(XTAL2{slash}TOSC2{slash}PCINT7))") (class "Default")
      (node (ref "IC4") (pin "10") (pinfunction "PB7(XTAL2/TOSC2/PCINT7)_10") (pintype "bidirectional"))
      (node (ref "X1") (pin "1") (pinfunction "1_1") (pintype "passive"))
    )
    (net (code "50") (name "Net-(IC5-QA)") (class "Default")
      (node (ref "IC5") (pin "15") (pinfunction "QA_15") (pintype "tri_state"))
      (node (ref "RN2") (pin "1") (pinfunction "1_1") (pintype "passive"))
    )
    (net (code "51") (name "Net-(IC5-QB)") (class "Default")
      (node (ref "IC5") (pin "1") (pinfunction "QB_1") (pintype "tri_state"))
      (node (ref "RN2") (pin "3") (pinfunction "1_3") (pintype "passive"))
    )
    (net (code "52") (name "Net-(IC5-QC)") (class "Default")
      (node (ref "IC5") (pin "2") (pinfunction "QC_2") (pintype "tri_state"))
      (node (ref "RN2") (pin "5") (pinfunction "1_5") (pintype "passive"))
    )
    (net (code "53") (name "Net-(IC5-QD)") (class "Default")
      (node (ref "IC5") (pin "3") (pinfunction "QD_3") (pintype "tri_state"))
      (node (ref "RN2") (pin "7") (pinfunction "1_7") (pintype "passive"))
    )
    (net (code "54") (name "Net-(IC5-QE)") (class "Default")
      (node (ref "IC5") (pin "4") (pinfunction "QE_4") (pintype "tri_state"))
      (node (ref "RN3") (pin "1") (pinfunction "1_1") (pintype "passive"))
    )
    (net (code "55") (name "Net-(IC5-QF)") (class "Default")
      (node (ref "IC5") (pin "5") (pinfunction "QF_5") (pintype "tri_state"))
      (node (ref "RN3") (pin "3") (pinfunction "1_3") (pintype "passive"))
    )
    (net (code "56") (name "Net-(IC5-QG)") (class "Default")
      (node (ref "IC5") (pin "6") (pinfunction "QG_6") (pintype "tri_state"))
      (node (ref "RN3") (pin "5") (pinfunction "1_5") (pintype "passive"))
    )
    (net (code "57") (name "Net-(IC5-QH)") (class "Default")
      (node (ref "IC5") (pin "7") (pinfunction "QH_7") (pintype "tri_state"))
      (node (ref "RN3") (pin "7") (pinfunction "1_7") (pintype "passive"))
    )
    (net (code "58") (name "Net-(IC6-LEDA)") (class "Default")
      (node (ref "IC6") (pin "27") (pinfunction "LEDA_27") (pintype "output"))
      (node (ref "R8") (pin "1") (pinfunction "1_1") (pintype "passive"))
    )
    (net (code "59") (name "Net-(IC6-LEDB)") (class "Default")
      (node (ref "IC6") (pin "26") (pinfunction "LEDB_26") (pintype "output"))
      (node (ref "R9") (pin "1") (pinfunction "1_1") (pintype "passive"))
    )
    (net (code "60") (name "Net-(IC6-OSC1)") (class "Default")
      (node (ref "CX2") (pin "1") (pinfunction "1_1") (pintype "passive"))
      (node (ref "IC6") (pin "23") (pinfunction "OSC1_23") (pintype "input"))
      (node (ref "X2") (pin "2") (pinfunction "2_2") (pintype "passive"))
    )
    (net (code "61") (name "Net-(IC6-OSC2)") (class "Default")
      (node (ref "CX1") (pin "1") (pinfunction "1_1") (pintype "passive"))
      (node (ref "IC6") (pin "24") (pinfunction "OSC2_24") (pintype "output"))
      (node (ref "X2") (pin "1") (pinfunction "1_1") (pintype "passive"))
    )
    (net (code "62") (name "Net-(IC6-RBIAS)") (class "Default")
      (node (ref "IC6") (pin "14") (pinfunction "RBIAS_14") (pintype "input"))
      (node (ref "R6") (pin "1") (pinfunction "1_1") (pintype "passive"))
    )
    (net (code "63") (name "Net-(IC6-VCAP)") (class "Default")
      (node (ref "C6") (pin "+") (pinfunction "+_+") (pintype "passive"))
      (node (ref "IC6") (pin "1") (pinfunction "VCAP_1") (pintype "input"))
    )
    (net (code "64") (name "Net-(J2-P)") (class "Default")
      (node (ref "J0") (pin "2") (pinfunction "2_2") (pintype "passive"))
      (node (ref "J2") (pin "2") (pinfunction "P_2") (pintype "passive"))
    )
    (net (code "65") (name "Net-(LCD-K)") (class "Default")
      (node (ref "LCD") (pin "16") (pinfunction "K_16") (pintype "input"))
      (node (ref "LCD") (pin "3") (pinfunction "VO_3") (pintype "input"))
      (node (ref "RLED") (pin "1") (pinfunction "1_1") (pintype "passive"))
    )
    (net (code "66") (name "Net-(R7-Pad1)") (class "Default")
      (node (ref "R7") (pin "1") (pinfunction "1_1") (pintype "passive"))
      (node (ref "RD-") (pin "2") (pinfunction "2_2") (pintype "passive"))
      (node (ref "USB") (pin "D-") (pinfunction "D-_D-") (pintype "bidirectional"))
    )
    (net (code "67") (name "Net-(RD+-Pad2)") (class "Default")
      (node (ref "RD+") (pin "2") (pinfunction "2_2") (pintype "passive"))
      (node (ref "USB") (pin "D+") (pinfunction "D+_D+") (pintype "bidirectional"))
    )
    (net (code "68") (name "Net-(RN2A-1)") (class "Default")
      (node (ref "RN2") (pin "2") (pinfunction "1_2") (pintype "passive"))
      (node (ref "T1") (pin "2") (pinfunction "G_2") (pintype "bidirectional"))
    )
    (net (code "69") (name "Net-(RN2C-1)") (class "Default")
      (node (ref "RN2") (pin "4") (pinfunction "1_4") (pintype "passive"))
      (node (ref "T2") (pin "2") (pinfunction "G_2") (pintype "bidirectional"))
    )
    (net (code "70") (name "Net-(RN2E-1)") (class "Default")
      (node (ref "RN2") (pin "6") (pinfunction "1_6") (pintype "passive"))
      (node (ref "T3") (pin "2") (pinfunction "G_2") (pintype "bidirectional"))
    )
    (net (code "71") (name "Net-(RN2G-1)") (class "Default")
      (node (ref "RN2") (pin "8") (pinfunction "1_8") (pintype "passive"))
      (node (ref "T4") (pin "2") (pinfunction "G_2") (pintype "bidirectional"))
    )
    (net (code "72") (name "Net-(RN3A-1)") (class "Default")
      (node (ref "RN3") (pin "2") (pinfunction "1_2") (pintype "passive"))
      (node (ref "T5") (pin "2") (pinfunction "G_2") (pintype "bidirectional"))
    )
    (net (code "73") (name "Net-(RN3C-1)") (class "Default")
      (node (ref "RN3") (pin "4") (pinfunction "1_4") (pintype "passive"))
      (node (ref "T6") (pin "2") (pinfunction "G_2") (pintype "bidirectional"))
    )
    (net (code "74") (name "Net-(RN3E-1)") (class "Default")
      (node (ref "RN3") (pin "6") (pinfunction "1_6") (pintype "passive"))
      (node (ref "T7") (pin "2") (pinfunction "G_2") (pintype "bidirectional"))
    )
    (net (code "75") (name "Net-(RN3G-1)") (class "Default")
      (node (ref "RN3") (pin "8") (pinfunction "1_8") (pintype "passive"))
      (node (ref "T8") (pin "2") (pinfunction "G_2") (pintype "bidirectional"))
    )
    (net (code "76") (name "Net-(T1-M2)") (class "Default")
      (node (ref "S12") (pin "1") (pinfunction "1_1") (pintype "passive"))
      (node (ref "T1") (pin "3") (pinfunction "M2_3") (pintype "bidirectional"))
    )
    (net (code "77") (name "Net-(T2-M2)") (class "Default")
      (node (ref "S12") (pin "2") (pinfunction "2_2") (pintype "passive"))
      (node (ref "T2") (pin "3") (pinfunction "M2_3") (pintype "bidirectional"))
    )
    (net (code "78") (name "Net-(T3-M2)") (class "Default")
      (node (ref "S34") (pin "1") (pinfunction "1_1") (pintype "passive"))
      (node (ref "T3") (pin "3") (pinfunction "M2_3") (pintype "bidirectional"))
    )
    (net (code "79") (name "Net-(T4-M2)") (class "Default")
      (node (ref "S34") (pin "2") (pinfunction "2_2") (pintype "passive"))
      (node (ref "T4") (pin "3") (pinfunction "M2_3") (pintype "bidirectional"))
    )
    (net (code "80") (name "Net-(T5-M2)") (class "Default")
      (node (ref "S56") (pin "1") (pinfunction "1_1") (pintype "passive"))
      (node (ref "T5") (pin "3") (pinfunction "M2_3") (pintype "bidirectional"))
    )
    (net (code "81") (name "Net-(T6-M2)") (class "Default")
      (node (ref "S56") (pin "2") (pinfunction "2_2") (pintype "passive"))
      (node (ref "T6") (pin "3") (pinfunction "M2_3") (pintype "bidirectional"))
    )
    (net (code "82") (name "Net-(T7-M2)") (class "Default")
      (node (ref "S78") (pin "1") (pinfunction "1_1") (pintype "passive"))
      (node (ref "T7") (pin "3") (pinfunction "M2_3") (pintype "bidirectional"))
    )
    (net (code "83") (name "Net-(T8-M2)") (class "Default")
      (node (ref "S78") (pin "2") (pinfunction "2_2") (pintype "passive"))
      (node (ref "T8") (pin "3") (pinfunction "M2_3") (pintype "bidirectional"))
    )
    (net (code "84") (name "VCC") (class "Default")
      (node (ref "C3") (pin "+") (pinfunction "+_+") (pintype "passive"))
      (node (ref "C4") (pin "1") (pinfunction "1_1") (pintype "passive"))
      (node (ref "C9") (pin "1") (pinfunction "1_1") (pintype "passive"))
      (node (ref "EXTOUT") (pin "1") (pinfunction "1_1") (pintype "passive"))
      (node (ref "IC2") (pin "3") (pinfunction "OUT_3") (pintype "passive"))
      (node (ref "IC4") (pin "20") (pinfunction "AVCC_20") (pintype "passive"))
      (node (ref "IC4") (pin "7") (pinfunction "VCC_7") (pintype "power_in"))
      (node (ref "IC5") (pin "10") (pinfunction "SCL_10") (pintype "input"))
      (node (ref "IC5") (pin "16") (pinfunction "VCC_16") (pintype "power_in"))
      (node (ref "IC6") (pin "15") (pinfunction "VDDTX_15") (pintype "input"))
      (node (ref "IC6") (pin "19") (pinfunction "VDDRX_19") (pintype "input"))
      (node (ref "IC6") (pin "20") (pinfunction "VDDPLL_20") (pintype "input"))
      (node (ref "IC6") (pin "25") (pinfunction "VDDOSC_25") (pintype "input"))
      (node (ref "IC6") (pin "28") (pinfunction "VDD_28") (pintype "input"))
      (node (ref "IC7") (pin "8") (pinfunction "VCC_8") (pintype "bidirectional"))
      (node (ref "IC8") (pin "VDD") (pinfunction "VCC_VDD") (pintype "power_in"))
      (node (ref "JP1") (pin "8") (pinfunction "8_8") (pintype "passive"))
      (node (ref "L2") (pin "2") (pinfunction "2_2") (pintype "passive"))
      (node (ref "R7") (pin "2") (pinfunction "2_2") (pintype "passive"))
      (node (ref "RN1") (pin "1") (pinfunction "1_1") (pintype "passive"))
      (node (ref "RN4") (pin "1") (pinfunction "1_1") (pintype "passive"))
      (node (ref "RN4") (pin "7") (pinfunction "1_7") (pintype "passive"))
    )
    (net (code "85") (name "unconnected-(IC3-SQW{slash}OUT-Pad7)") (class "Default")
      (node (ref "IC3") (pin "7") (pinfunction "SQW/OUT_7") (pintype "bidirectional"))
    )
    (net (code "86") (name "unconnected-(IC6-CLKOUT-Pad3)") (class "Default")
      (node (ref "IC6") (pin "3") (pinfunction "CLKOUT_3") (pintype "output"))
    )
    (net (code "87") (name "unconnected-(IC6-NC*-Pad5)") (class "Default")
      (node (ref "IC6") (pin "5") (pinfunction "NC*_5") (pintype "output"))
    )
    (net (code "88") (name "unconnected-(IC6-~{INT}-Pad4)") (class "Default")
      (node (ref "IC6") (pin "4") (pinfunction "~{INT}_4") (pintype "output"))
    )
    (net (code "89") (name "unconnected-(IC8-PadANT)") (class "Default")
      (node (ref "IC8") (pin "ANT") (pinfunction "ANT_ANT") (pintype "passive"))
    )
    (net (code "90") (name "unconnected-(IC8-PadFFS)") (class "Default")
      (node (ref "IC8") (pin "FFS") (pinfunction "FFS_FFS") (pintype "bidirectional"))
    )
    (net (code "91") (name "unconnected-(J2-O-Pad1)") (class "Default")
      (node (ref "J2") (pin "1") (pinfunction "O_1") (pintype "passive"))
    )
    (net (code "92") (name "unconnected-(LCD-DB0-Pad7)") (class "Default")
      (node (ref "LCD") (pin "7") (pinfunction "DB0_7") (pintype "bidirectional"))
    )
    (net (code "93") (name "unconnected-(LCD-DB1-Pad8)") (class "Default")
      (node (ref "LCD") (pin "8") (pinfunction "DB1_8") (pintype "bidirectional"))
    )
    (net (code "94") (name "unconnected-(LCD-DB2-Pad9)") (class "Default")
      (node (ref "LCD") (pin "9") (pinfunction "DB2_9") (pintype "bidirectional"))
    )
    (net (code "95") (name "unconnected-(LCD-DB3-Pad10)") (class "Default")
      (node (ref "LCD") (pin "10") (pinfunction "DB3_10") (pintype "bidirectional"))
    )
    (net (code "96") (name "unconnected-(RJ1-PadNC)") (class "Default")
      (node (ref "RJ1") (pin "NC") (pinfunction "NC_NC") (pintype "bidirectional"))
    )
    (net (code "97") (name "unconnected-(RJ1-PadP5)") (class "Default")
      (node (ref "RJ1") (pin "P5") (pinfunction "P5_P5") (pintype "bidirectional"))
    )
  )
)
